# FPGA_DDR3_IO.net
KiCad netlist of a schematic drawn in Altium Designer
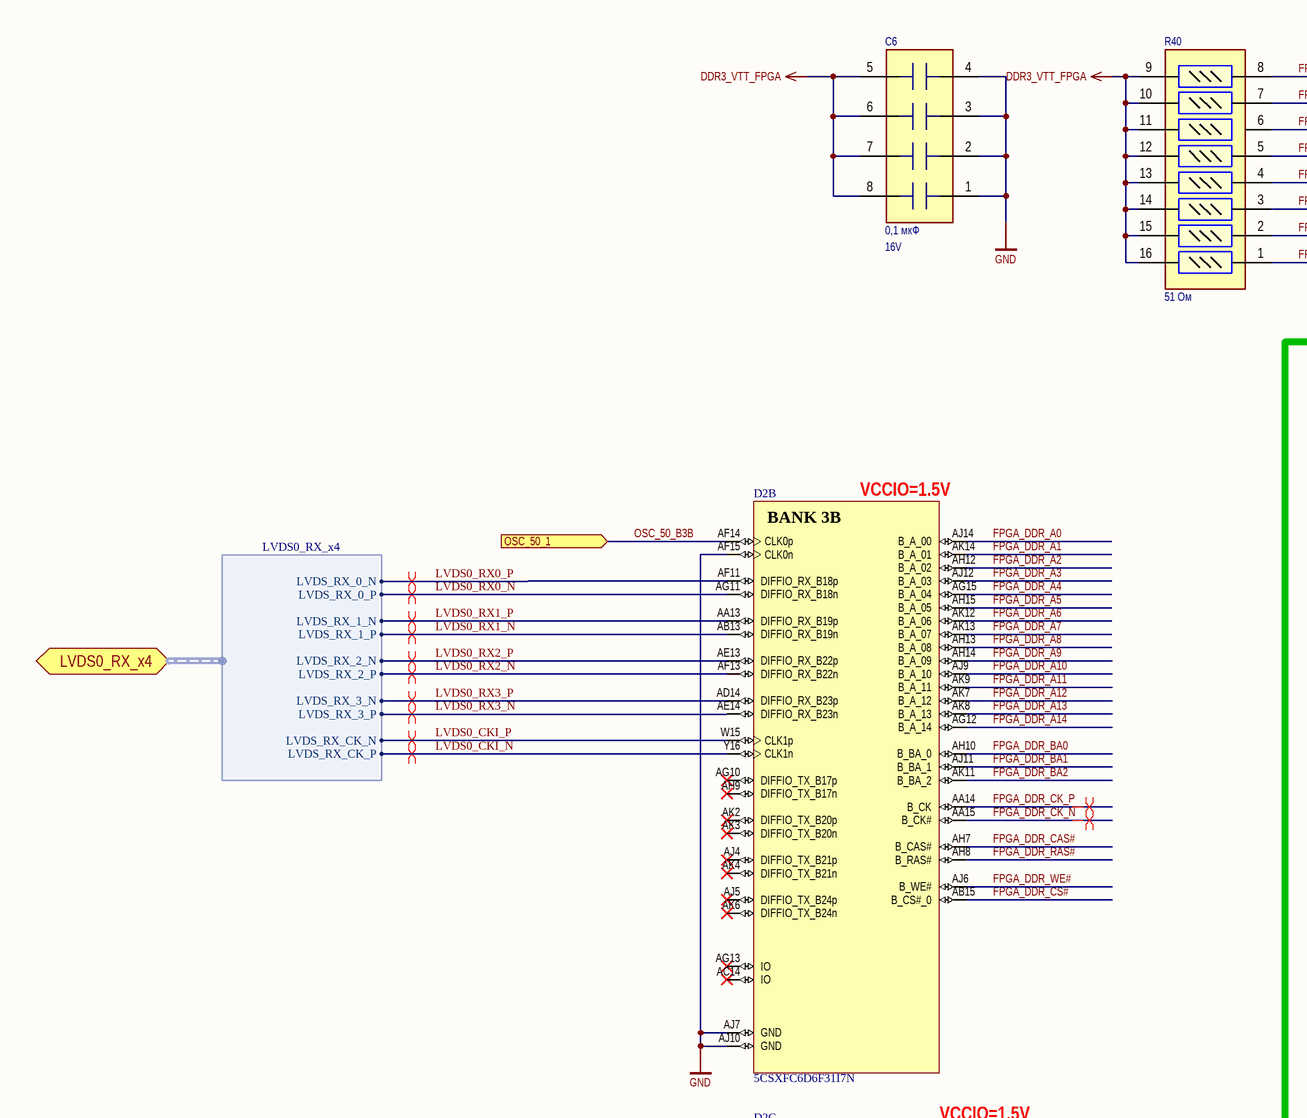
[diagram p0: FPGA_DDR3&IO.SchDoc, top left]
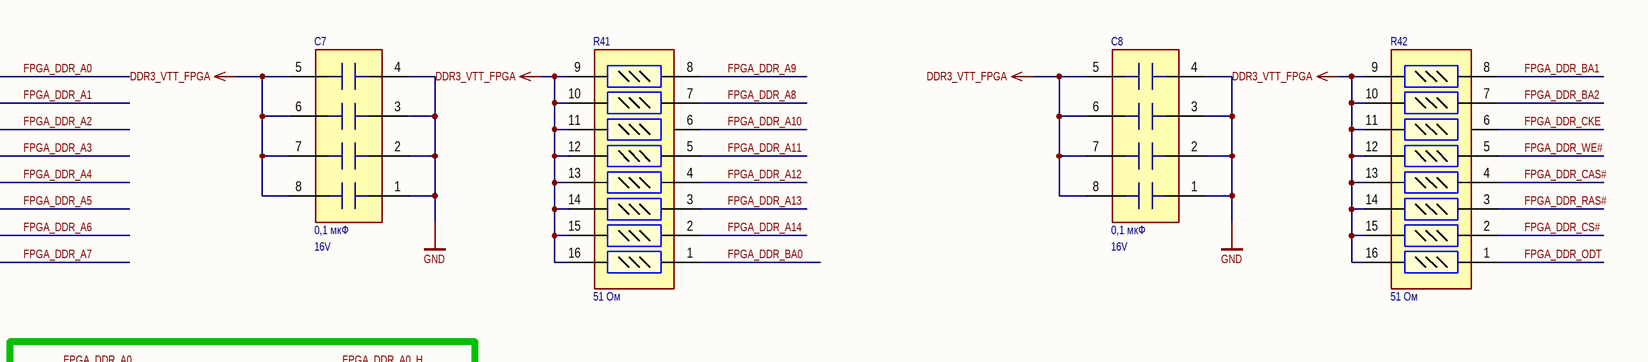
[diagram p1: FPGA_DDR3&IO.SchDoc, top right]
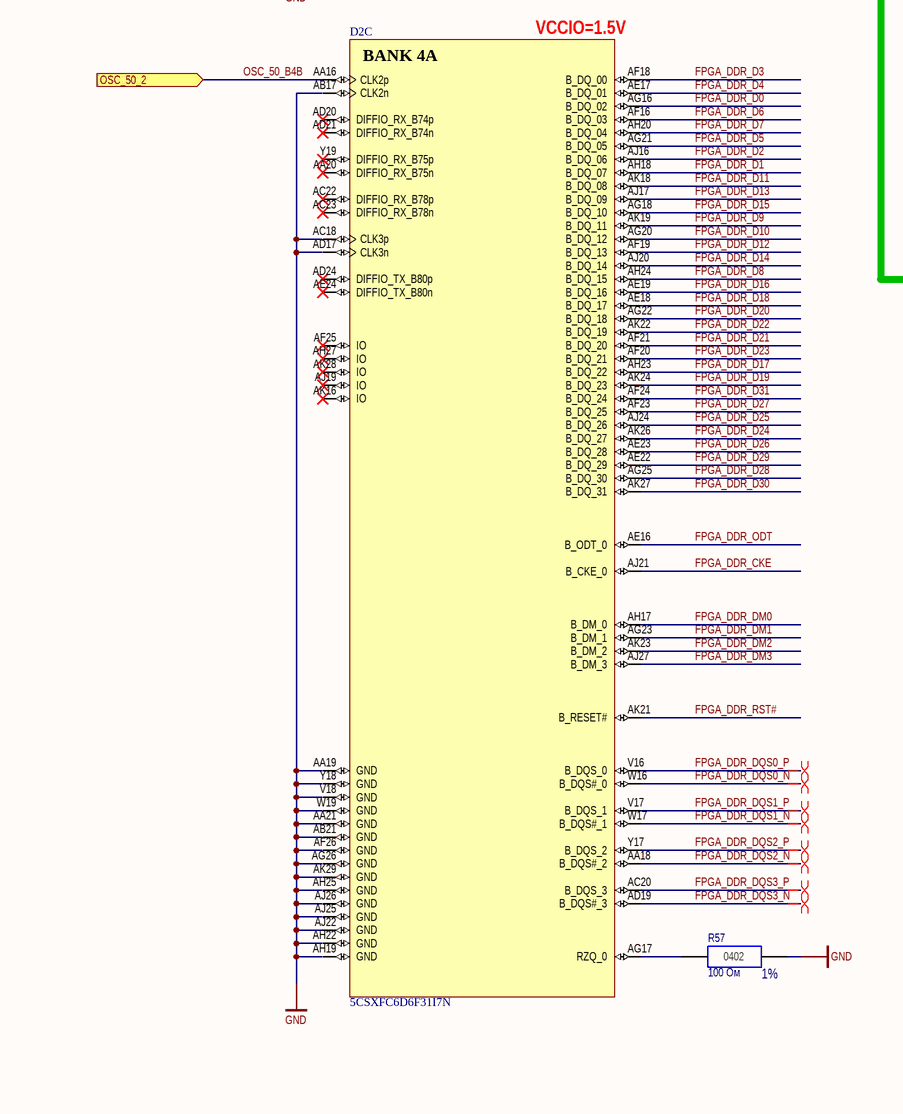
[diagram p2: FPGA_DDR3&IO.SchDoc, bottom left]
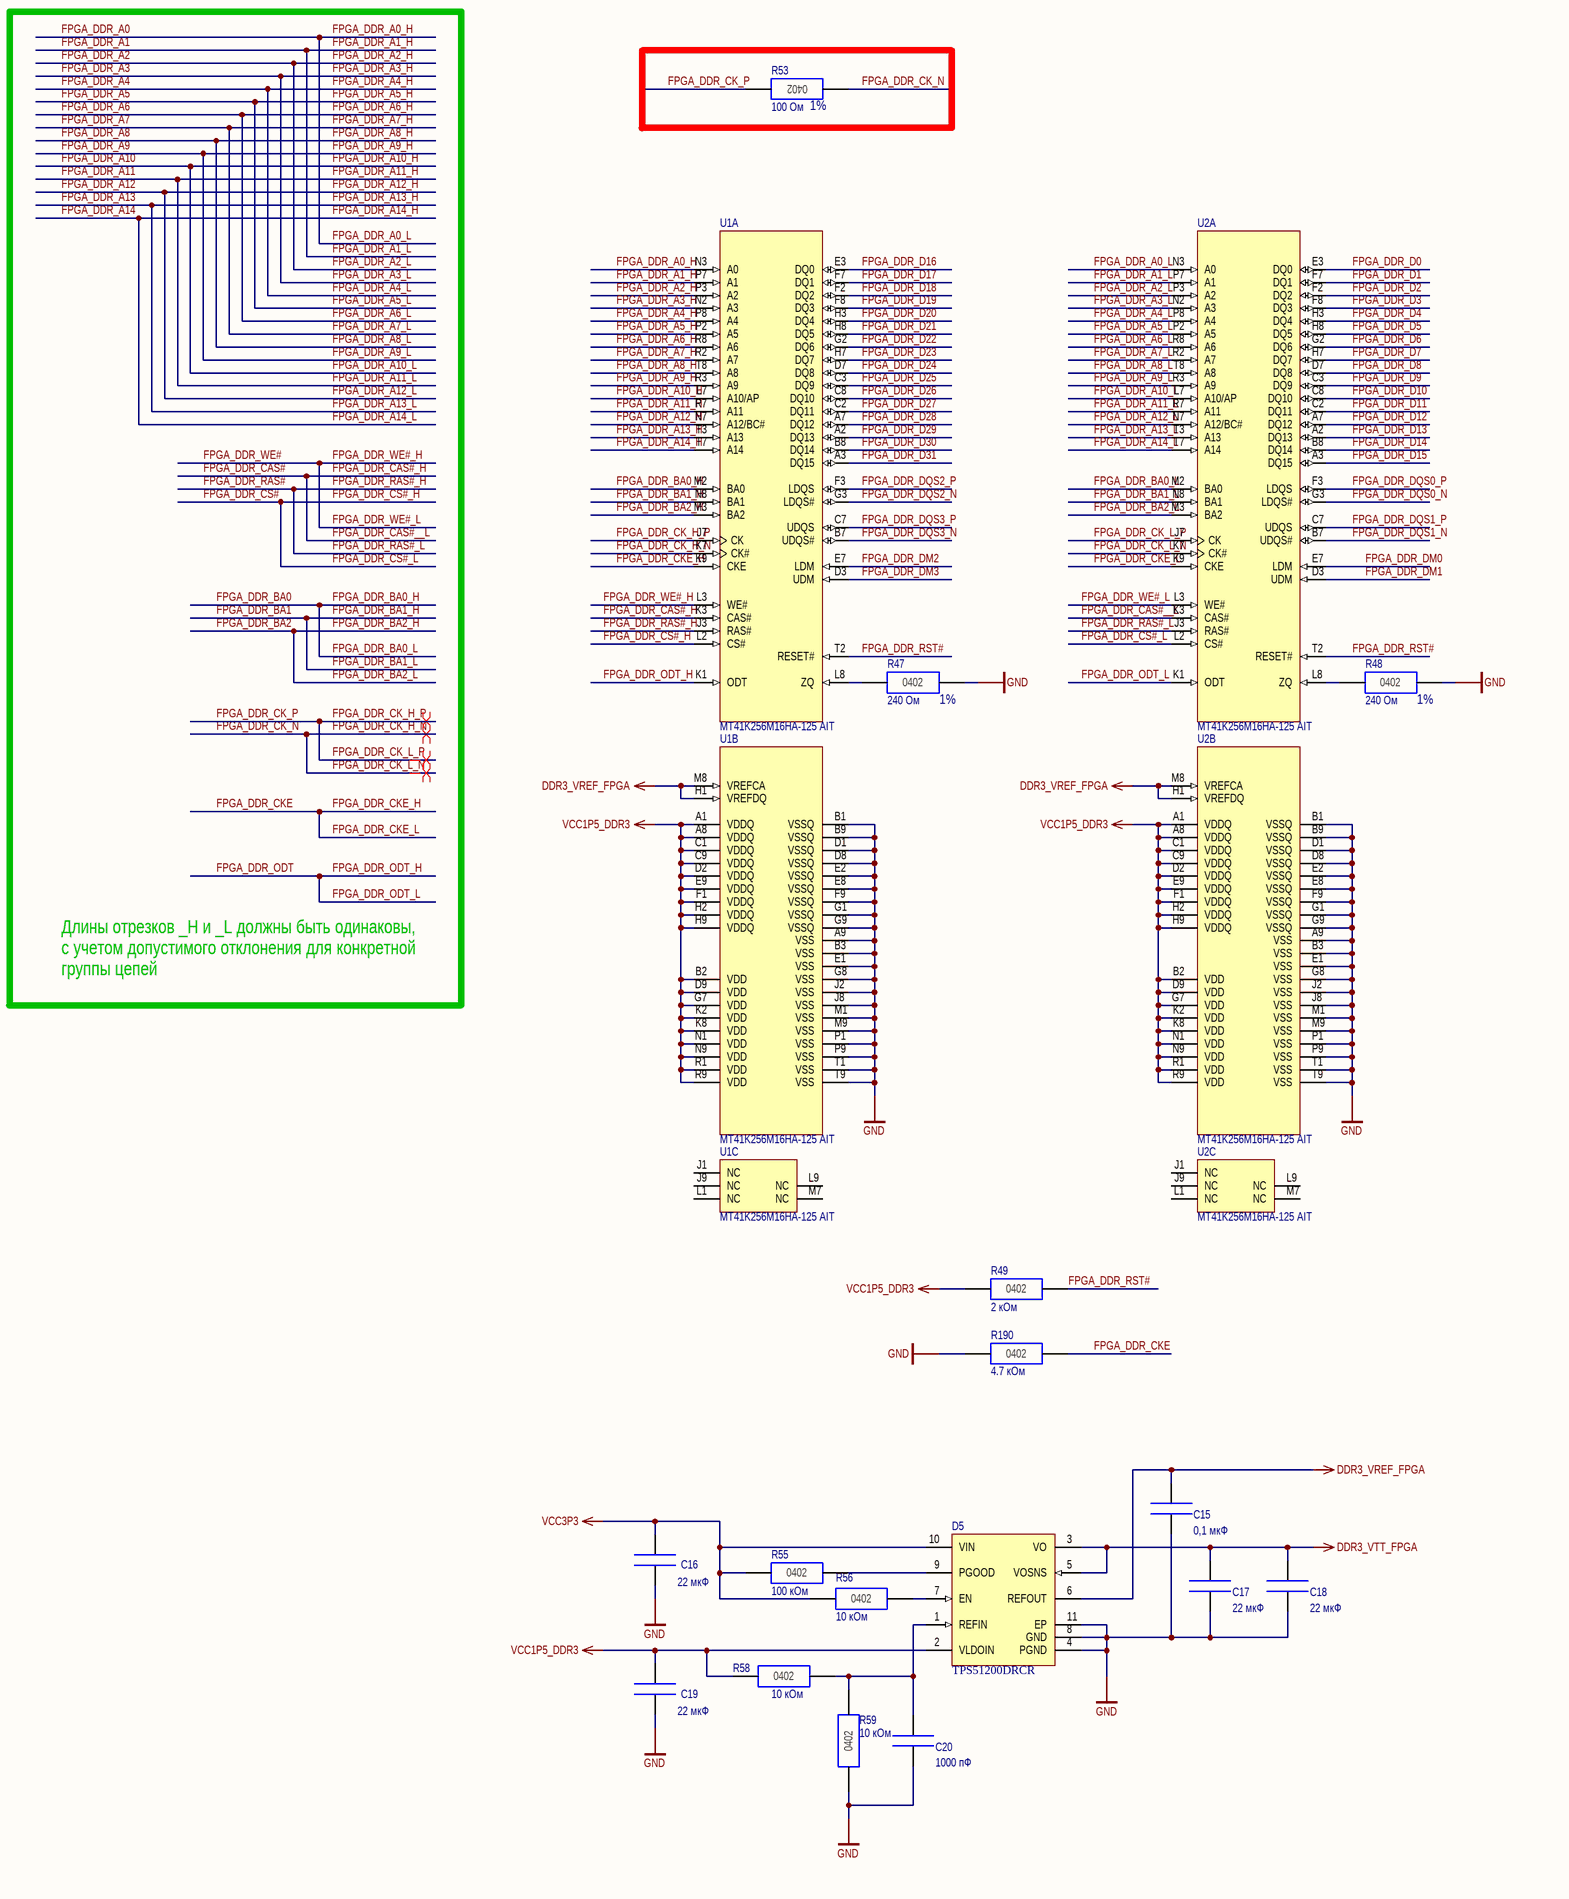
[diagram p3: FPGA_DDR3&IO.SchDoc, bottom right]

(export (version "E")
  (design (tool "Eeschema 10.0.6"))
  (components
    (comp (ref "C6")
      (value "0,1 мкФ")
      (footprint "CAF-80P319X159-8N")
      (description "Чип конденсатор керамический")
      (fields (field (name "V") "16V") (field (name "Comment") "W3A4YC104KAT2A"))
      (libsource (lib "SD_IC") (part "W3A4YC104KAT2A"))
    )
    (comp (ref "C7")
      (value "0,1 мкФ")
      (footprint "CAF-80P319X159-8N")
      (description "Чип конденсатор керамический")
      (fields (field (name "V") "16V") (field (name "Comment") "W3A4YC104KAT2A"))
      (libsource (lib "SD_IC") (part "W3A4YC104KAT2A"))
    )
    (comp (ref "C8")
      (value "0,1 мкФ")
      (footprint "CAF-80P319X159-8N")
      (description "Чип конденсатор керамический")
      (fields (field (name "V") "16V") (field (name "Comment") "W3A4YC104KAT2A"))
      (libsource (lib "SD_IC") (part "W3A4YC104KAT2A"))
    )
    (comp (ref "C15")
      (value "0,1 мкФ")
      (footprint "CC0402(1005)")
      (description "Чип конденсатор керамический")
      (fields (field (name "Comment") "CC0402-X7R-0,1 мкФ-20%-10В"))
      (libsource (lib "Чип конденсаторы") (part "CC0402-X7R-#-20%-10В"))
    )
    (comp (ref "C16")
      (value "22 мкФ")
      (footprint "CC0402(1005)")
      (description "Чип конденсатор керамический")
      (fields (field (name "Comment") "CC0402-X5R-22 мкФ-20%-6.3В"))
      (libsource (lib "Чип конденсаторы") (part "CC0402-X7R-#-20%-10В"))
    )
    (comp (ref "C17")
      (value "22 мкФ")
      (footprint "CC0402(1005)")
      (description "Чип конденсатор керамический")
      (fields (field (name "Comment") "CC0402-X5R-22 мкФ-20%-6.3В"))
      (libsource (lib "Чип конденсаторы") (part "CC0402-X7R-#-20%-10В"))
    )
    (comp (ref "C18")
      (value "22 мкФ")
      (footprint "CC0402(1005)")
      (description "Чип конденсатор керамический")
      (fields (field (name "Comment") "CC0402-X5R-22 мкФ-20%-6.3В"))
      (libsource (lib "Чип конденсаторы") (part "CC0402-X7R-#-20%-10В"))
    )
    (comp (ref "C19")
      (value "22 мкФ")
      (footprint "CC0402(1005)")
      (description "Чип конденсатор керамический")
      (fields (field (name "Comment") "CC0402-X5R-22 мкФ-20%-6.3В"))
      (libsource (lib "Чип конденсаторы") (part "CC0402-X7R-#-20%-10В"))
    )
    (comp (ref "C20")
      (value "1000 пФ")
      (footprint "CC0402(1005)")
      (description "Чип конденсатор керамический")
      (fields (field (name "Comment") "CC0402-NP01000 пФ-1%-50В"))
      (libsource (lib "Чип конденсаторы") (part "CC0402-X7R-#-20%-10В"))
    )
    (comp (ref "D2")
      (value "5CSXFC6D6F31I7N")
      (footprint "ALTR-FBGA896_A-200")
      (fields (field (name "MANUFACTURER") "Altera"))
      (libsource (lib "") (part "5CSXFC6D6F31I7N_1"))
    )
    (comp (ref "D5")
      (value "TPS51200DRCR")
      (footprint "TI-DRC10-2400X1650TP_V")
      (fields (field (name "MANUFACTURER") "Texas Instruments"))
      (libsource (lib "SD_IC") (part "TPS51200DRCR"))
    )
    (comp (ref "R40")
      (value "51 Ом")
      (footprint "YC248")
      (description "Набор чип резисторов")
      (fields (field (name "Comment") "YC248-JR-07-51 Ом"))
      (libsource (lib "SD_IC") (part "YC248-JR-07-#"))
    )
    (comp (ref "R41")
      (value "51 Ом")
      (footprint "VOU_SOM_Vlad:YC248")
      (description "Набор чип резисторов")
      (fields (field (name "Comment") "YC248-JR-07-51 Ом"))
      (libsource (lib "SD_IC") (part "YC248-JR-07-#"))
    )
    (comp (ref "R42")
      (value "51 Ом")
      (footprint "YC248")
      (description "Набор чип резисторов")
      (fields (field (name "Comment") "YC248-JR-07-51 Ом"))
      (libsource (lib "SD_IC") (part "YC248-JR-07-#"))
    )
    (comp (ref "R47")
      (value "240 Ом")
      (footprint "CR0402(1005)")
      (description "Чип резистор")
      (fields (field (name "TOLERANCE") "1%") (field (name "Comment") "CR0402-240 Ом-±TOLERANCE"))
      (libsource (lib "Резисторы") (part "CR0402-#-±5%"))
    )
    (comp (ref "R48")
      (value "240 Ом")
      (footprint "CR0402(1005)")
      (description "Чип резистор")
      (fields (field (name "TOLERANCE") "1%") (field (name "Comment") "CR0402-240 Ом-±TOLERANCE"))
      (libsource (lib "Резисторы") (part "CR0402-#-±5%"))
    )
    (comp (ref "R49")
      (value "2 кОм")
      (footprint "CR0402(1005)")
      (description "Чип резистор")
      (fields (field (name "TOLERANCE") "5%") (field (name "Comment") "CR0402-2 кОм-±5%"))
      (libsource (lib "Резисторы") (part "CR0402-#-±5%"))
    )
    (comp (ref "R53")
      (value "100 Ом")
      (footprint "CR0402(1005)")
      (description "Чип резистор")
      (fields (field (name "TOLERANCE") "1%") (field (name "Comment") "CR0402-100 Ом-±TOLERANCE"))
      (libsource (lib "") (part "CR0402-#-±5%_1"))
    )
    (comp (ref "R55")
      (value "100 кОм")
      (footprint "CR0402(1005)")
      (description "Чип резистор")
      (fields (field (name "TOLERANCE") "5%") (field (name "Comment") "CR0402-100 кОм-±5%"))
      (libsource (lib "Резисторы") (part "CR0402-#-±5%"))
    )
    (comp (ref "R56")
      (value "10 кОм")
      (footprint "CR0402(1005)")
      (description "Чип резистор")
      (fields (field (name "TOLERANCE") "5%") (field (name "Comment") "CR0402-10 кОм-±5%"))
      (libsource (lib "Резисторы") (part "CR0402-#-±5%"))
    )
    (comp (ref "R57")
      (value "100 Ом")
      (footprint "CC0402(1005)_OCT")
      (description "Чип резистор")
      (fields (field (name "TOLERANCE") "1%") (field (name "Comment") "CR0402-100 Ом-±TOLERANCE"))
      (libsource (lib "Резисторы") (part "CR0402-#-±5%"))
    )
    (comp (ref "R58")
      (value "10 кОм")
      (footprint "CR0402(1005)")
      (description "Чип резистор")
      (fields (field (name "TOLERANCE") "5%") (field (name "Comment") "CR0402-10 кОм-±5%"))
      (libsource (lib "Резисторы") (part "CR0402-#-±5%"))
    )
    (comp (ref "R59")
      (value "10 кОм")
      (footprint "CR0402(1005)")
      (description "Чип резистор")
      (fields (field (name "TOLERANCE") "5%") (field (name "Comment") "CR0402-10 кОм-±5%"))
      (libsource (lib "") (part "CR0402-#-±5%_2"))
    )
    (comp (ref "R190")
      (value "4.7 кОм")
      (footprint "CR0402(1005)")
      (description "Чип резистор")
      (fields (field (name "TOLERANCE") "5%") (field (name "Comment") "CR0402-4.7 кОм-±5%"))
      (libsource (lib "Резисторы") (part "CR0402-#-±5%"))
    )
    (comp (ref "U1")
      (value "MT41K256M16HA-125 AIT")
      (footprint "MICT-HA-96")
      (description "4Gb DDR3-1600 SDRAM, 256Mb x 16, 1.25ns, 1.35V, -40 to 95 degC, 96-Ball FBGA, Pb-Free")
      (fields (field (name "VOLTAGE") "1.35V ") (field (name "MANUFACTURER") "Micron"))
      (libsource (lib "SD_IC") (part "MT41K256M16HA-125 AIT"))
    )
    (comp (ref "U2")
      (value "MT41K256M16HA-125 AIT")
      (footprint "MICT-HA-96")
      (description "4Gb DDR3-1600 SDRAM, 256Mb x 16, 1.25ns, 1.35V, -40 to 95 degC, 96-Ball FBGA, Pb-Free")
      (fields (field (name "VOLTAGE") "1.35V ") (field (name "MANUFACTURER") "Micron"))
      (libsource (lib "SD_IC") (part "MT41K256M16HA-125 AIT"))
    )
  )
  (nets
    (net (code "2") (name "/FPGA_DDR_A0") (class "Default")
      (node (ref "D2") (pin "AJ14") (pinfunction "B_A_00_AJ14") (pintype "bidirectional"))
      (node (ref "R40") (pin "8") (pintype "passive"))
      (node (ref "U1") (pin "N3") (pinfunction "A0_N3") (pintype "input"))
      (node (ref "U2") (pin "N3") (pinfunction "A0_N3") (pintype "input"))
    )
    (net (code "3") (name "/FPGA_DDR_A1") (class "Default")
      (node (ref "D2") (pin "AK14") (pinfunction "B_A_01_AK14") (pintype "bidirectional"))
      (node (ref "R40") (pin "7") (pintype "passive"))
      (node (ref "U1") (pin "P7") (pinfunction "A1_P7") (pintype "input"))
      (node (ref "U2") (pin "P7") (pinfunction "A1_P7") (pintype "input"))
    )
    (net (code "4") (name "/FPGA_DDR_A2") (class "Default")
      (node (ref "D2") (pin "AH12") (pinfunction "B_A_02_AH12") (pintype "bidirectional"))
      (node (ref "R40") (pin "6") (pintype "passive"))
      (node (ref "U1") (pin "P3") (pinfunction "A2_P3") (pintype "input"))
      (node (ref "U2") (pin "P3") (pinfunction "A2_P3") (pintype "input"))
    )
    (net (code "5") (name "/FPGA_DDR_A3") (class "Default")
      (node (ref "D2") (pin "AJ12") (pinfunction "B_A_03_AJ12") (pintype "bidirectional"))
      (node (ref "R40") (pin "5") (pintype "passive"))
      (node (ref "U1") (pin "N2") (pinfunction "A3_N2") (pintype "input"))
      (node (ref "U2") (pin "N2") (pinfunction "A3_N2") (pintype "input"))
    )
    (net (code "6") (name "/FPGA_DDR_A4") (class "Default")
      (node (ref "D2") (pin "AG15") (pinfunction "B_A_04_AG15") (pintype "bidirectional"))
      (node (ref "R40") (pin "4") (pintype "passive"))
      (node (ref "U1") (pin "P8") (pinfunction "A4_P8") (pintype "input"))
      (node (ref "U2") (pin "P8") (pinfunction "A4_P8") (pintype "input"))
    )
    (net (code "7") (name "/FPGA_DDR_A5") (class "Default")
      (node (ref "D2") (pin "AH15") (pinfunction "B_A_05_AH15") (pintype "bidirectional"))
      (node (ref "R40") (pin "3") (pintype "passive"))
      (node (ref "U1") (pin "P2") (pinfunction "A5_P2") (pintype "input"))
      (node (ref "U2") (pin "P2") (pinfunction "A5_P2") (pintype "input"))
    )
    (net (code "8") (name "/FPGA_DDR_A6") (class "Default")
      (node (ref "D2") (pin "AK12") (pinfunction "B_A_06_AK12") (pintype "bidirectional"))
      (node (ref "R40") (pin "2") (pintype "passive"))
      (node (ref "U1") (pin "R8") (pinfunction "A6_R8") (pintype "input"))
      (node (ref "U2") (pin "R8") (pinfunction "A6_R8") (pintype "input"))
    )
    (net (code "9") (name "/FPGA_DDR_A7") (class "Default")
      (node (ref "D2") (pin "AK13") (pinfunction "B_A_07_AK13") (pintype "bidirectional"))
      (node (ref "R40") (pin "1") (pintype "passive"))
      (node (ref "U1") (pin "R2") (pinfunction "A7_R2") (pintype "input"))
      (node (ref "U2") (pin "R2") (pinfunction "A7_R2") (pintype "input"))
    )
    (net (code "10") (name "/FPGA_DDR_A8") (class "Default")
      (node (ref "D2") (pin "AH13") (pinfunction "B_A_08_AH13") (pintype "bidirectional"))
      (node (ref "R41") (pin "7") (pintype "passive"))
      (node (ref "U1") (pin "T8") (pinfunction "A8_T8") (pintype "input"))
      (node (ref "U2") (pin "T8") (pinfunction "A8_T8") (pintype "input"))
    )
    (net (code "11") (name "/FPGA_DDR_A9") (class "Default")
      (node (ref "D2") (pin "AH14") (pinfunction "B_A_09_AH14") (pintype "bidirectional"))
      (node (ref "R41") (pin "8") (pintype "passive"))
      (node (ref "U1") (pin "R3") (pinfunction "A9_R3") (pintype "input"))
      (node (ref "U2") (pin "R3") (pinfunction "A9_R3") (pintype "input"))
    )
    (net (code "12") (name "/FPGA_DDR_A10") (class "Default")
      (node (ref "D2") (pin "AJ9") (pinfunction "B_A_10_AJ9") (pintype "bidirectional"))
      (node (ref "R41") (pin "6") (pintype "passive"))
      (node (ref "U1") (pin "L7") (pinfunction "A10/AP_L7") (pintype "input"))
      (node (ref "U2") (pin "L7") (pinfunction "A10/AP_L7") (pintype "input"))
    )
    (net (code "13") (name "/FPGA_DDR_A11") (class "Default")
      (node (ref "D2") (pin "AK9") (pinfunction "B_A_11_AK9") (pintype "bidirectional"))
      (node (ref "R41") (pin "5") (pintype "passive"))
      (node (ref "U1") (pin "R7") (pinfunction "A11_R7") (pintype "input"))
      (node (ref "U2") (pin "R7") (pinfunction "A11_R7") (pintype "input"))
    )
    (net (code "14") (name "/FPGA_DDR_A12") (class "Default")
      (node (ref "D2") (pin "AK7") (pinfunction "B_A_12_AK7") (pintype "bidirectional"))
      (node (ref "R41") (pin "4") (pintype "passive"))
      (node (ref "U1") (pin "N7") (pinfunction "A12/BC#_N7") (pintype "input"))
      (node (ref "U2") (pin "N7") (pinfunction "A12/BC#_N7") (pintype "input"))
    )
    (net (code "15") (name "/FPGA_DDR_A13") (class "Default")
      (node (ref "D2") (pin "AK8") (pinfunction "B_A_13_AK8") (pintype "bidirectional"))
      (node (ref "R41") (pin "3") (pintype "passive"))
      (node (ref "U1") (pin "T3") (pinfunction "A13_T3") (pintype "input"))
      (node (ref "U2") (pin "T3") (pinfunction "A13_T3") (pintype "input"))
    )
    (net (code "16") (name "/FPGA_DDR_A14") (class "Default")
      (node (ref "D2") (pin "AG12") (pinfunction "B_A_14_AG12") (pintype "bidirectional"))
      (node (ref "R41") (pin "2") (pintype "passive"))
      (node (ref "U1") (pin "T7") (pinfunction "A14_T7") (pintype "input"))
      (node (ref "U2") (pin "T7") (pinfunction "A14_T7") (pintype "input"))
    )
    (net (code "17") (name "/FPGA_DDR_BA0") (class "Default")
      (node (ref "D2") (pin "AH10") (pinfunction "B_BA_0_AH10") (pintype "bidirectional"))
      (node (ref "R41") (pin "1") (pintype "passive"))
      (node (ref "U1") (pin "M2") (pinfunction "BA0_M2") (pintype "input"))
      (node (ref "U2") (pin "M2") (pinfunction "BA0_M2") (pintype "input"))
    )
    (net (code "18") (name "/FPGA_DDR_BA1") (class "Default")
      (node (ref "D2") (pin "AJ11") (pinfunction "B_BA_1_AJ11") (pintype "bidirectional"))
      (node (ref "R42") (pin "8") (pintype "passive"))
      (node (ref "U1") (pin "N8") (pinfunction "BA1_N8") (pintype "input"))
      (node (ref "U2") (pin "N8") (pinfunction "BA1_N8") (pintype "input"))
    )
    (net (code "19") (name "/FPGA_DDR_BA2") (class "Default")
      (node (ref "D2") (pin "AK11") (pinfunction "B_BA_2_AK11") (pintype "bidirectional"))
      (node (ref "R42") (pin "7") (pintype "passive"))
      (node (ref "U1") (pin "M3") (pinfunction "BA2_M3") (pintype "input"))
      (node (ref "U2") (pin "M3") (pinfunction "BA2_M3") (pintype "input"))
    )
    (net (code "20") (name "/FPGA_DDR_CAS#") (class "Default")
      (node (ref "D2") (pin "AH7") (pinfunction "B_CAS#_AH7") (pintype "bidirectional"))
      (node (ref "R42") (pin "4") (pintype "passive"))
      (node (ref "U1") (pin "K3") (pinfunction "CAS#_K3") (pintype "input"))
      (node (ref "U2") (pin "K3") (pinfunction "CAS#_K3") (pintype "input"))
    )
    (net (code "21") (name "/FPGA_DDR_CKE") (class "Default")
      (node (ref "D2") (pin "AJ21") (pinfunction "B_CKE_0_AJ21") (pintype "bidirectional"))
      (node (ref "R190") (pin "2") (pinfunction "-_2") (pintype "passive"))
      (node (ref "R42") (pin "6") (pintype "passive"))
      (node (ref "U1") (pin "K9") (pinfunction "CKE_K9") (pintype "input"))
      (node (ref "U2") (pin "K9") (pinfunction "CKE_K9") (pintype "input"))
    )
    (net (code "22") (name "/FPGA_DDR_CK_H_N") (class "Default")
      (node (ref "D2") (pin "AA15") (pinfunction "B_CK#_AA15") (pintype "bidirectional"))
      (node (ref "R53") (pin "1") (pinfunction "+_1") (pintype "passive"))
      (node (ref "U1") (pin "K7") (pinfunction "CK#_K7") (pintype "input"))
      (node (ref "U2") (pin "K7") (pinfunction "CK#_K7") (pintype "input"))
    )
    (net (code "23") (name "/FPGA_DDR_CK_H_P") (class "Default")
      (node (ref "D2") (pin "AA14") (pinfunction "B_CK_AA14") (pintype "bidirectional"))
      (node (ref "R53") (pin "2") (pinfunction "-_2") (pintype "passive"))
      (node (ref "U1") (pin "J7") (pinfunction "CK_J7") (pintype "input"))
      (node (ref "U2") (pin "J7") (pinfunction "CK_J7") (pintype "input"))
    )
    (net (code "24") (name "/FPGA_DDR_CS#") (class "Default")
      (node (ref "D2") (pin "AB15") (pinfunction "B_CS#_0_AB15") (pintype "bidirectional"))
      (node (ref "R42") (pin "2") (pintype "passive"))
      (node (ref "U1") (pin "L2") (pinfunction "CS#_L2") (pintype "input"))
      (node (ref "U2") (pin "L2") (pinfunction "CS#_L2") (pintype "input"))
    )
    (net (code "25") (name "/FPGA_DDR_D0") (class "Default")
      (node (ref "D2") (pin "AG16") (pinfunction "B_DQ_02_AG16") (pintype "bidirectional"))
      (node (ref "U2") (pin "E3") (pinfunction "DQ0_E3") (pintype "bidirectional"))
    )
    (net (code "26") (name "/FPGA_DDR_D1") (class "Default")
      (node (ref "D2") (pin "AH18") (pinfunction "B_DQ_07_AH18") (pintype "bidirectional"))
      (node (ref "U2") (pin "F7") (pinfunction "DQ1_F7") (pintype "bidirectional"))
    )
    (net (code "27") (name "/FPGA_DDR_D2") (class "Default")
      (node (ref "D2") (pin "AJ16") (pinfunction "B_DQ_06_AJ16") (pintype "bidirectional"))
      (node (ref "U2") (pin "F2") (pinfunction "DQ2_F2") (pintype "bidirectional"))
    )
    (net (code "28") (name "/FPGA_DDR_D3") (class "Default")
      (node (ref "D2") (pin "AF18") (pinfunction "B_DQ_00_AF18") (pintype "bidirectional"))
      (node (ref "U2") (pin "F8") (pinfunction "DQ3_F8") (pintype "bidirectional"))
    )
    (net (code "29") (name "/FPGA_DDR_D4") (class "Default")
      (node (ref "D2") (pin "AE17") (pinfunction "B_DQ_01_AE17") (pintype "bidirectional"))
      (node (ref "U2") (pin "H3") (pinfunction "DQ4_H3") (pintype "bidirectional"))
    )
    (net (code "30") (name "/FPGA_DDR_D5") (class "Default")
      (node (ref "D2") (pin "AG21") (pinfunction "B_DQ_05_AG21") (pintype "bidirectional"))
      (node (ref "U2") (pin "H8") (pinfunction "DQ5_H8") (pintype "bidirectional"))
    )
    (net (code "31") (name "/FPGA_DDR_D6") (class "Default")
      (node (ref "D2") (pin "AF16") (pinfunction "B_DQ_03_AF16") (pintype "bidirectional"))
      (node (ref "U2") (pin "G2") (pinfunction "DQ6_G2") (pintype "bidirectional"))
    )
    (net (code "32") (name "/FPGA_DDR_D7") (class "Default")
      (node (ref "D2") (pin "AH20") (pinfunction "B_DQ_04_AH20") (pintype "bidirectional"))
      (node (ref "U2") (pin "H7") (pinfunction "DQ7_H7") (pintype "bidirectional"))
    )
    (net (code "33") (name "/FPGA_DDR_D8") (class "Default")
      (node (ref "D2") (pin "AH24") (pinfunction "B_DQ_15_AH24") (pintype "bidirectional"))
      (node (ref "U2") (pin "D7") (pinfunction "DQ8_D7") (pintype "bidirectional"))
    )
    (net (code "34") (name "/FPGA_DDR_D9") (class "Default")
      (node (ref "D2") (pin "AK19") (pinfunction "B_DQ_11_AK19") (pintype "bidirectional"))
      (node (ref "U2") (pin "C3") (pinfunction "DQ9_C3") (pintype "bidirectional"))
    )
    (net (code "35") (name "/FPGA_DDR_D10") (class "Default")
      (node (ref "D2") (pin "AG20") (pinfunction "B_DQ_12_AG20") (pintype "bidirectional"))
      (node (ref "U2") (pin "C8") (pinfunction "DQ10_C8") (pintype "bidirectional"))
    )
    (net (code "36") (name "/FPGA_DDR_D11") (class "Default")
      (node (ref "D2") (pin "AK18") (pinfunction "B_DQ_08_AK18") (pintype "bidirectional"))
      (node (ref "U2") (pin "C2") (pinfunction "DQ11_C2") (pintype "bidirectional"))
    )
    (net (code "37") (name "/FPGA_DDR_D12") (class "Default")
      (node (ref "D2") (pin "AF19") (pinfunction "B_DQ_13_AF19") (pintype "bidirectional"))
      (node (ref "U2") (pin "A7") (pinfunction "DQ12_A7") (pintype "bidirectional"))
    )
    (net (code "38") (name "/FPGA_DDR_D13") (class "Default")
      (node (ref "D2") (pin "AJ17") (pinfunction "B_DQ_09_AJ17") (pintype "bidirectional"))
      (node (ref "U2") (pin "A2") (pinfunction "DQ13_A2") (pintype "bidirectional"))
    )
    (net (code "39") (name "/FPGA_DDR_D14") (class "Default")
      (node (ref "D2") (pin "AJ20") (pinfunction "B_DQ_14_AJ20") (pintype "bidirectional"))
      (node (ref "U2") (pin "B8") (pinfunction "DQ14_B8") (pintype "bidirectional"))
    )
    (net (code "40") (name "/FPGA_DDR_D15") (class "Default")
      (node (ref "D2") (pin "AG18") (pinfunction "B_DQ_10_AG18") (pintype "bidirectional"))
      (node (ref "U2") (pin "A3") (pinfunction "DQ15_A3") (pintype "bidirectional"))
    )
    (net (code "41") (name "/FPGA_DDR_D16") (class "Default")
      (node (ref "D2") (pin "AE19") (pinfunction "B_DQ_16_AE19") (pintype "bidirectional"))
      (node (ref "U1") (pin "E3") (pinfunction "DQ0_E3") (pintype "bidirectional"))
    )
    (net (code "42") (name "/FPGA_DDR_D17") (class "Default")
      (node (ref "D2") (pin "AH23") (pinfunction "B_DQ_22_AH23") (pintype "bidirectional"))
      (node (ref "U1") (pin "F7") (pinfunction "DQ1_F7") (pintype "bidirectional"))
    )
    (net (code "43") (name "/FPGA_DDR_D18") (class "Default")
      (node (ref "D2") (pin "AE18") (pinfunction "B_DQ_17_AE18") (pintype "bidirectional"))
      (node (ref "U1") (pin "F2") (pinfunction "DQ2_F2") (pintype "bidirectional"))
    )
    (net (code "44") (name "/FPGA_DDR_D19") (class "Default")
      (node (ref "D2") (pin "AK24") (pinfunction "B_DQ_23_AK24") (pintype "bidirectional"))
      (node (ref "U1") (pin "F8") (pinfunction "DQ3_F8") (pintype "bidirectional"))
    )
    (net (code "45") (name "/FPGA_DDR_D20") (class "Default")
      (node (ref "D2") (pin "AG22") (pinfunction "B_DQ_18_AG22") (pintype "bidirectional"))
      (node (ref "U1") (pin "H3") (pinfunction "DQ4_H3") (pintype "bidirectional"))
    )
    (net (code "46") (name "/FPGA_DDR_D21") (class "Default")
      (node (ref "D2") (pin "AF21") (pinfunction "B_DQ_20_AF21") (pintype "bidirectional"))
      (node (ref "U1") (pin "H8") (pinfunction "DQ5_H8") (pintype "bidirectional"))
    )
    (net (code "47") (name "/FPGA_DDR_D22") (class "Default")
      (node (ref "D2") (pin "AK22") (pinfunction "B_DQ_19_AK22") (pintype "bidirectional"))
      (node (ref "U1") (pin "G2") (pinfunction "DQ6_G2") (pintype "bidirectional"))
    )
    (net (code "48") (name "/FPGA_DDR_D23") (class "Default")
      (node (ref "D2") (pin "AF20") (pinfunction "B_DQ_21_AF20") (pintype "bidirectional"))
      (node (ref "U1") (pin "H7") (pinfunction "DQ7_H7") (pintype "bidirectional"))
    )
    (net (code "49") (name "/FPGA_DDR_D24") (class "Default")
      (node (ref "D2") (pin "AK26") (pinfunction "B_DQ_27_AK26") (pintype "bidirectional"))
      (node (ref "U1") (pin "D7") (pinfunction "DQ8_D7") (pintype "bidirectional"))
    )
    (net (code "50") (name "/FPGA_DDR_D25") (class "Default")
      (node (ref "D2") (pin "AJ24") (pinfunction "B_DQ_26_AJ24") (pintype "bidirectional"))
      (node (ref "U1") (pin "C3") (pinfunction "DQ9_C3") (pintype "bidirectional"))
    )
    (net (code "51") (name "/FPGA_DDR_D26") (class "Default")
      (node (ref "D2") (pin "AE23") (pinfunction "B_DQ_28_AE23") (pintype "bidirectional"))
      (node (ref "U1") (pin "C8") (pinfunction "DQ10_C8") (pintype "bidirectional"))
    )
    (net (code "52") (name "/FPGA_DDR_D27") (class "Default")
      (node (ref "D2") (pin "AF23") (pinfunction "B_DQ_25_AF23") (pintype "bidirectional"))
      (node (ref "U1") (pin "C2") (pinfunction "DQ11_C2") (pintype "bidirectional"))
    )
    (net (code "53") (name "/FPGA_DDR_D28") (class "Default")
      (node (ref "D2") (pin "AG25") (pinfunction "B_DQ_30_AG25") (pintype "bidirectional"))
      (node (ref "U1") (pin "A7") (pinfunction "DQ12_A7") (pintype "bidirectional"))
    )
    (net (code "54") (name "/FPGA_DDR_D29") (class "Default")
      (node (ref "D2") (pin "AE22") (pinfunction "B_DQ_29_AE22") (pintype "bidirectional"))
      (node (ref "U1") (pin "A2") (pinfunction "DQ13_A2") (pintype "bidirectional"))
    )
    (net (code "55") (name "/FPGA_DDR_D30") (class "Default")
      (node (ref "D2") (pin "AK27") (pinfunction "B_DQ_31_AK27") (pintype "bidirectional"))
      (node (ref "U1") (pin "B8") (pinfunction "DQ14_B8") (pintype "bidirectional"))
    )
    (net (code "56") (name "/FPGA_DDR_D31") (class "Default")
      (node (ref "D2") (pin "AF24") (pinfunction "B_DQ_24_AF24") (pintype "bidirectional"))
      (node (ref "U1") (pin "A3") (pinfunction "DQ15_A3") (pintype "bidirectional"))
    )
    (net (code "57") (name "/FPGA_DDR_DM0") (class "Default")
      (node (ref "D2") (pin "AH17") (pinfunction "B_DM_0_AH17") (pintype "bidirectional"))
      (node (ref "U2") (pin "E7") (pinfunction "LDM_E7") (pintype "input"))
    )
    (net (code "58") (name "/FPGA_DDR_DM1") (class "Default")
      (node (ref "D2") (pin "AG23") (pinfunction "B_DM_1_AG23") (pintype "bidirectional"))
      (node (ref "U2") (pin "D3") (pinfunction "UDM_D3") (pintype "input"))
    )
    (net (code "59") (name "/FPGA_DDR_DM2") (class "Default")
      (node (ref "D2") (pin "AK23") (pinfunction "B_DM_2_AK23") (pintype "bidirectional"))
      (node (ref "U1") (pin "E7") (pinfunction "LDM_E7") (pintype "input"))
    )
    (net (code "60") (name "/FPGA_DDR_DM3") (class "Default")
      (node (ref "D2") (pin "AJ27") (pinfunction "B_DM_3_AJ27") (pintype "bidirectional"))
      (node (ref "U1") (pin "D3") (pinfunction "UDM_D3") (pintype "input"))
    )
    (net (code "61") (name "/FPGA_DDR_DQS0_N") (class "Default")
      (node (ref "D2") (pin "W16") (pinfunction "B_DQS#_0_W16") (pintype "bidirectional"))
      (node (ref "U2") (pin "G3") (pinfunction "LDQS#_G3") (pintype "bidirectional"))
    )
    (net (code "62") (name "/FPGA_DDR_DQS0_P") (class "Default")
      (node (ref "D2") (pin "V16") (pinfunction "B_DQS_0_V16") (pintype "bidirectional"))
      (node (ref "U2") (pin "F3") (pinfunction "LDQS_F3") (pintype "bidirectional"))
    )
    (net (code "63") (name "/FPGA_DDR_DQS1_N") (class "Default")
      (node (ref "D2") (pin "W17") (pinfunction "B_DQS#_1_W17") (pintype "bidirectional"))
      (node (ref "U2") (pin "B7") (pinfunction "UDQS#_B7") (pintype "bidirectional"))
    )
    (net (code "64") (name "/FPGA_DDR_DQS1_P") (class "Default")
      (node (ref "D2") (pin "V17") (pinfunction "B_DQS_1_V17") (pintype "bidirectional"))
      (node (ref "U2") (pin "C7") (pinfunction "UDQS_C7") (pintype "bidirectional"))
    )
    (net (code "65") (name "/FPGA_DDR_DQS2_N") (class "Default")
      (node (ref "D2") (pin "AA18") (pinfunction "B_DQS#_2_AA18") (pintype "bidirectional"))
      (node (ref "U1") (pin "G3") (pinfunction "LDQS#_G3") (pintype "bidirectional"))
    )
    (net (code "66") (name "/FPGA_DDR_DQS2_P") (class "Default")
      (node (ref "D2") (pin "Y17") (pinfunction "B_DQS_2_Y17") (pintype "bidirectional"))
      (node (ref "U1") (pin "F3") (pinfunction "LDQS_F3") (pintype "bidirectional"))
    )
    (net (code "67") (name "/FPGA_DDR_DQS3_N") (class "Default")
      (node (ref "D2") (pin "AD19") (pinfunction "B_DQS#_3_AD19") (pintype "bidirectional"))
      (node (ref "U1") (pin "B7") (pinfunction "UDQS#_B7") (pintype "bidirectional"))
    )
    (net (code "68") (name "/FPGA_DDR_DQS3_P") (class "Default")
      (node (ref "D2") (pin "AC20") (pinfunction "B_DQS_3_AC20") (pintype "bidirectional"))
      (node (ref "U1") (pin "C7") (pinfunction "UDQS_C7") (pintype "bidirectional"))
    )
    (net (code "69") (name "/FPGA_DDR_ODT") (class "Default")
      (node (ref "D2") (pin "AE16") (pinfunction "B_ODT_0_AE16") (pintype "bidirectional"))
      (node (ref "R42") (pin "1") (pintype "passive"))
      (node (ref "U1") (pin "K1") (pinfunction "ODT_K1") (pintype "input"))
      (node (ref "U2") (pin "K1") (pinfunction "ODT_K1") (pintype "input"))
    )
    (net (code "70") (name "/FPGA_DDR_RAS#") (class "Default")
      (node (ref "D2") (pin "AH8") (pinfunction "B_RAS#_AH8") (pintype "bidirectional"))
      (node (ref "R42") (pin "3") (pintype "passive"))
      (node (ref "U1") (pin "J3") (pinfunction "RAS#_J3") (pintype "input"))
      (node (ref "U2") (pin "J3") (pinfunction "RAS#_J3") (pintype "input"))
    )
    (net (code "71") (name "/FPGA_DDR_RST#") (class "Default")
      (node (ref "D2") (pin "AK21") (pinfunction "B_RESET#_AK21") (pintype "bidirectional"))
      (node (ref "R49") (pin "2") (pinfunction "-_2") (pintype "passive"))
      (node (ref "U1") (pin "T2") (pinfunction "RESET#_T2") (pintype "input"))
      (node (ref "U2") (pin "T2") (pinfunction "RESET#_T2") (pintype "input"))
    )
    (net (code "72") (name "/FPGA_DDR_WE#") (class "Default")
      (node (ref "D2") (pin "AJ6") (pinfunction "B_WE#_AJ6") (pintype "bidirectional"))
      (node (ref "R42") (pin "5") (pintype "passive"))
      (node (ref "U1") (pin "L3") (pinfunction "WE#_L3") (pintype "input"))
      (node (ref "U2") (pin "L3") (pinfunction "WE#_L3") (pintype "input"))
    )
    (net (code "74") (name "/LVDS0_CKI_P") (class "Default")
      (node (ref "D2") (pin "W15") (pinfunction "CLK1p_W15") (pintype "bidirectional"))
    )
    (net (code "76") (name "/LVDS0_RX0_P") (class "Default")
      (node (ref "D2") (pin "AF11") (pinfunction "DIFFIO_RX_B18p_AF11") (pintype "bidirectional"))
    )
    (net (code "77") (name "/LVDS0_RX1_N") (class "Default")
      (node (ref "D2") (pin "AB13") (pinfunction "DIFFIO_RX_B19n_AB13") (pintype "bidirectional"))
    )
    (net (code "78") (name "/LVDS0_RX1_P") (class "Default")
      (node (ref "D2") (pin "AA13") (pinfunction "DIFFIO_RX_B19p_AA13") (pintype "bidirectional"))
    )
    (net (code "79") (name "/LVDS0_RX2_N") (class "Default")
      (node (ref "D2") (pin "AF13") (pinfunction "DIFFIO_RX_B22n_AF13") (pintype "bidirectional"))
    )
    (net (code "80") (name "/LVDS0_RX2_P") (class "Default")
      (node (ref "D2") (pin "AE13") (pinfunction "DIFFIO_RX_B22p_AE13") (pintype "bidirectional"))
    )
    (net (code "82") (name "/LVDS0_RX3_N") (class "Default")
      (node (ref "D2") (pin "AE14") (pinfunction "DIFFIO_RX_B23n_AE14") (pintype "bidirectional"))
    )
    (net (code "83") (name "/LVDS0_RX3_P") (class "Default")
      (node (ref "D2") (pin "AD14") (pinfunction "DIFFIO_RX_B23p_AD14") (pintype "bidirectional"))
    )
    (net (code "84") (name "/OSC_50_B3B") (class "Default")
      (node (ref "D2") (pin "AF14") (pinfunction "CLK0p_AF14") (pintype "bidirectional"))
    )
    (net (code "86") (name "/OSC_50_B4B") (class "Default")
      (node (ref "D2") (pin "AA16") (pinfunction "CLK2p_AA16") (pintype "bidirectional"))
    )
    (net (code "87") (name "DDR3_VREF_FPGA") (class "Default")
      (node (ref "C15") (pin "1") (pinfunction "+_1") (pintype "passive"))
      (node (ref "D5") (pin "6") (pinfunction "REFOUT_6") (pintype "power_in"))
      (node (ref "U1") (pin "H1") (pinfunction "VREFDQ_H1") (pintype "input"))
      (node (ref "U1") (pin "M8") (pinfunction "VREFCA_M8") (pintype "input"))
      (node (ref "U2") (pin "H1") (pinfunction "VREFDQ_H1") (pintype "input"))
      (node (ref "U2") (pin "M8") (pinfunction "VREFCA_M8") (pintype "input"))
    )
    (net (code "88") (name "DDR3_VTT_FPGA") (class "Default")
      (node (ref "C17") (pin "1") (pinfunction "+_1") (pintype "passive"))
      (node (ref "C18") (pin "1") (pinfunction "+_1") (pintype "passive"))
      (node (ref "C6") (pin "5") (pintype "passive"))
      (node (ref "C6") (pin "6") (pintype "passive"))
      (node (ref "C6") (pin "7") (pintype "passive"))
      (node (ref "C6") (pin "8") (pintype "passive"))
      (node (ref "C7") (pin "5") (pintype "passive"))
      (node (ref "C7") (pin "6") (pintype "passive"))
      (node (ref "C7") (pin "7") (pintype "passive"))
      (node (ref "C7") (pin "8") (pintype "passive"))
      (node (ref "C8") (pin "5") (pintype "passive"))
      (node (ref "C8") (pin "6") (pintype "passive"))
      (node (ref "C8") (pin "7") (pintype "passive"))
      (node (ref "C8") (pin "8") (pintype "passive"))
      (node (ref "D5") (pin "3") (pinfunction "VO_3") (pintype "power_in"))
      (node (ref "D5") (pin "5") (pinfunction "VOSNS_5") (pintype "input"))
      (node (ref "R40") (pin "10") (pintype "passive"))
      (node (ref "R40") (pin "11") (pintype "passive"))
      (node (ref "R40") (pin "12") (pintype "passive"))
      (node (ref "R40") (pin "13") (pintype "passive"))
      (node (ref "R40") (pin "14") (pintype "passive"))
      (node (ref "R40") (pin "15") (pintype "passive"))
      (node (ref "R40") (pin "16") (pintype "passive"))
      (node (ref "R40") (pin "9") (pintype "passive"))
      (node (ref "R41") (pin "10") (pintype "passive"))
      (node (ref "R41") (pin "11") (pintype "passive"))
      (node (ref "R41") (pin "12") (pintype "passive"))
      (node (ref "R41") (pin "13") (pintype "passive"))
      (node (ref "R41") (pin "14") (pintype "passive"))
      (node (ref "R41") (pin "15") (pintype "passive"))
      (node (ref "R41") (pin "16") (pintype "passive"))
      (node (ref "R41") (pin "9") (pintype "passive"))
      (node (ref "R42") (pin "10") (pintype "passive"))
      (node (ref "R42") (pin "11") (pintype "passive"))
      (node (ref "R42") (pin "12") (pintype "passive"))
      (node (ref "R42") (pin "13") (pintype "passive"))
      (node (ref "R42") (pin "14") (pintype "passive"))
      (node (ref "R42") (pin "15") (pintype "passive"))
      (node (ref "R42") (pin "16") (pintype "passive"))
      (node (ref "R42") (pin "9") (pintype "passive"))
    )
    (net (code "89") (name "GND") (class "Default")
      (node (ref "C15") (pin "2") (pinfunction "-_2") (pintype "passive"))
      (node (ref "C16") (pin "2") (pinfunction "-_2") (pintype "passive"))
      (node (ref "C17") (pin "2") (pinfunction "-_2") (pintype "passive"))
      (node (ref "C18") (pin "2") (pinfunction "-_2") (pintype "passive"))
      (node (ref "C19") (pin "2") (pinfunction "-_2") (pintype "passive"))
      (node (ref "C20") (pin "2") (pinfunction "-_2") (pintype "passive"))
      (node (ref "C6") (pin "1") (pintype "passive"))
      (node (ref "C6") (pin "2") (pintype "passive"))
      (node (ref "C6") (pin "3") (pintype "passive"))
      (node (ref "C6") (pin "4") (pintype "passive"))
      (node (ref "C7") (pin "1") (pintype "passive"))
      (node (ref "C7") (pin "2") (pintype "passive"))
      (node (ref "C7") (pin "3") (pintype "passive"))
      (node (ref "C7") (pin "4") (pintype "passive"))
      (node (ref "C8") (pin "1") (pintype "passive"))
      (node (ref "C8") (pin "2") (pintype "passive"))
      (node (ref "C8") (pin "3") (pintype "passive"))
      (node (ref "C8") (pin "4") (pintype "passive"))
      (node (ref "D2") (pin "AF15") (pinfunction "CLK0n_AF15") (pintype "bidirectional"))
      (node (ref "D2") (pin "AJ10") (pinfunction "GND_AJ10") (pintype "bidirectional"))
      (node (ref "D2") (pin "AJ22") (pinfunction "GND_AJ22") (pintype "bidirectional"))
      (node (ref "D2") (pin "AJ7") (pinfunction "GND_AJ7") (pintype "bidirectional"))
      (node (ref "D5") (pin "11") (pinfunction "EP_11") (pintype "power_in"))
      (node (ref "D5") (pin "4") (pinfunction "PGND_4") (pintype "power_in"))
      (node (ref "D5") (pin "8") (pinfunction "GND_8") (pintype "power_in"))
      (node (ref "R190") (pin "1") (pinfunction "+_1") (pintype "passive"))
      (node (ref "R47") (pin "2") (pinfunction "-_2") (pintype "passive"))
      (node (ref "R48") (pin "2") (pinfunction "-_2") (pintype "passive"))
      (node (ref "R57") (pin "2") (pinfunction "-_2") (pintype "passive"))
      (node (ref "R59") (pin "1") (pinfunction "+_1") (pintype "passive"))
      (node (ref "U1") (pin "A9") (pinfunction "VSS_A9") (pintype "power_in"))
      (node (ref "U1") (pin "B1") (pinfunction "VSSQ_B1") (pintype "power_in"))
      (node (ref "U1") (pin "B3") (pinfunction "VSS_B3") (pintype "power_in"))
      (node (ref "U1") (pin "B9") (pinfunction "VSSQ_B9") (pintype "power_in"))
      (node (ref "U1") (pin "D1") (pinfunction "VSSQ_D1") (pintype "power_in"))
      (node (ref "U1") (pin "D8") (pinfunction "VSSQ_D8") (pintype "power_in"))
      (node (ref "U1") (pin "E1") (pinfunction "VSS_E1") (pintype "power_in"))
      (node (ref "U1") (pin "E2") (pinfunction "VSSQ_E2") (pintype "power_in"))
      (node (ref "U1") (pin "E8") (pinfunction "VSSQ_E8") (pintype "power_in"))
      (node (ref "U1") (pin "F9") (pinfunction "VSSQ_F9") (pintype "power_in"))
      (node (ref "U1") (pin "G1") (pinfunction "VSSQ_G1") (pintype "power_in"))
      (node (ref "U1") (pin "G8") (pinfunction "VSS_G8") (pintype "power_in"))
      (node (ref "U1") (pin "G9") (pinfunction "VSSQ_G9") (pintype "power_in"))
      (node (ref "U1") (pin "J2") (pinfunction "VSS_J2") (pintype "power_in"))
      (node (ref "U1") (pin "J8") (pinfunction "VSS_J8") (pintype "power_in"))
      (node (ref "U1") (pin "M1") (pinfunction "VSS_M1") (pintype "power_in"))
      (node (ref "U1") (pin "M9") (pinfunction "VSS_M9") (pintype "power_in"))
      (node (ref "U1") (pin "P1") (pinfunction "VSS_P1") (pintype "power_in"))
      (node (ref "U1") (pin "P9") (pinfunction "VSS_P9") (pintype "power_in"))
      (node (ref "U1") (pin "T1") (pinfunction "VSS_T1") (pintype "power_in"))
      (node (ref "U1") (pin "T9") (pinfunction "VSS_T9") (pintype "power_in"))
      (node (ref "U2") (pin "A9") (pinfunction "VSS_A9") (pintype "power_in"))
      (node (ref "U2") (pin "B1") (pinfunction "VSSQ_B1") (pintype "power_in"))
      (node (ref "U2") (pin "B3") (pinfunction "VSS_B3") (pintype "power_in"))
      (node (ref "U2") (pin "B9") (pinfunction "VSSQ_B9") (pintype "power_in"))
      (node (ref "U2") (pin "D1") (pinfunction "VSSQ_D1") (pintype "power_in"))
      (node (ref "U2") (pin "D8") (pinfunction "VSSQ_D8") (pintype "power_in"))
      (node (ref "U2") (pin "E1") (pinfunction "VSS_E1") (pintype "power_in"))
      (node (ref "U2") (pin "E2") (pinfunction "VSSQ_E2") (pintype "power_in"))
      (node (ref "U2") (pin "E8") (pinfunction "VSSQ_E8") (pintype "power_in"))
      (node (ref "U2") (pin "F9") (pinfunction "VSSQ_F9") (pintype "power_in"))
      (node (ref "U2") (pin "G1") (pinfunction "VSSQ_G1") (pintype "power_in"))
      (node (ref "U2") (pin "G8") (pinfunction "VSS_G8") (pintype "power_in"))
      (node (ref "U2") (pin "G9") (pinfunction "VSSQ_G9") (pintype "power_in"))
      (node (ref "U2") (pin "J2") (pinfunction "VSS_J2") (pintype "power_in"))
      (node (ref "U2") (pin "J8") (pinfunction "VSS_J8") (pintype "power_in"))
      (node (ref "U2") (pin "M1") (pinfunction "VSS_M1") (pintype "power_in"))
      (node (ref "U2") (pin "M9") (pinfunction "VSS_M9") (pintype "power_in"))
      (node (ref "U2") (pin "P1") (pinfunction "VSS_P1") (pintype "power_in"))
      (node (ref "U2") (pin "P9") (pinfunction "VSS_P9") (pintype "power_in"))
      (node (ref "U2") (pin "T1") (pinfunction "VSS_T1") (pintype "power_in"))
      (node (ref "U2") (pin "T9") (pinfunction "VSS_T9") (pintype "power_in"))
    )
    (net (code "90") (name "Net-(C20-+)") (class "Default")
      (node (ref "C20") (pin "1") (pinfunction "+_1") (pintype "passive"))
      (node (ref "D5") (pin "1") (pinfunction "REFIN_1") (pintype "input"))
      (node (ref "R58") (pin "2") (pinfunction "-_2") (pintype "passive"))
      (node (ref "R59") (pin "2") (pinfunction "-_2") (pintype "passive"))
    )
    (net (code "91") (name "Net-(D2C-RZQ_0)") (class "Default")
      (node (ref "D2") (pin "AG17") (pinfunction "RZQ_0_AG17") (pintype "bidirectional"))
      (node (ref "R57") (pin "1") (pinfunction "+_1") (pintype "passive"))
    )
    (net (code "92") (name "Net-(D5-EN)") (class "Default")
      (node (ref "D5") (pin "7") (pinfunction "EN_7") (pintype "input"))
      (node (ref "R56") (pin "2") (pinfunction "-_2") (pintype "passive"))
    )
    (net (code "93") (name "Net-(D5-PGOOD)") (class "Default")
      (node (ref "D5") (pin "9") (pinfunction "PGOOD_9") (pintype "open_collector"))
      (node (ref "R55") (pin "2") (pinfunction "-_2") (pintype "passive"))
    )
    (net (code "94") (name "Net-(R47-+)") (class "Default")
      (node (ref "R47") (pin "1") (pinfunction "+_1") (pintype "passive"))
      (node (ref "U1") (pin "L8") (pinfunction "ZQ_L8") (pintype "input"))
    )
    (net (code "95") (name "Net-(R48-+)") (class "Default")
      (node (ref "R48") (pin "1") (pinfunction "+_1") (pintype "passive"))
      (node (ref "U2") (pin "L8") (pinfunction "ZQ_L8") (pintype "input"))
    )
    (net (code "96") (name "VCC1P5_DDR3") (class "Default")
      (node (ref "C19") (pin "1") (pinfunction "+_1") (pintype "passive"))
      (node (ref "D5") (pin "2") (pinfunction "VLDOIN_2") (pintype "power_in"))
      (node (ref "R49") (pin "1") (pinfunction "+_1") (pintype "passive"))
      (node (ref "R58") (pin "1") (pinfunction "+_1") (pintype "passive"))
      (node (ref "U1") (pin "A1") (pinfunction "VDDQ_A1") (pintype "power_in"))
      (node (ref "U1") (pin "A8") (pinfunction "VDDQ_A8") (pintype "power_in"))
      (node (ref "U1") (pin "B2") (pinfunction "VDD_B2") (pintype "power_in"))
      (node (ref "U1") (pin "C1") (pinfunction "VDDQ_C1") (pintype "power_in"))
      (node (ref "U1") (pin "C9") (pinfunction "VDDQ_C9") (pintype "power_in"))
      (node (ref "U1") (pin "D2") (pinfunction "VDDQ_D2") (pintype "power_in"))
      (node (ref "U1") (pin "D9") (pinfunction "VDD_D9") (pintype "power_in"))
      (node (ref "U1") (pin "E9") (pinfunction "VDDQ_E9") (pintype "power_in"))
      (node (ref "U1") (pin "F1") (pinfunction "VDDQ_F1") (pintype "power_in"))
      (node (ref "U1") (pin "G7") (pinfunction "VDD_G7") (pintype "power_in"))
      (node (ref "U1") (pin "H2") (pinfunction "VDDQ_H2") (pintype "power_in"))
      (node (ref "U1") (pin "H9") (pinfunction "VDDQ_H9") (pintype "power_in"))
      (node (ref "U1") (pin "K2") (pinfunction "VDD_K2") (pintype "power_in"))
      (node (ref "U1") (pin "K8") (pinfunction "VDD_K8") (pintype "power_in"))
      (node (ref "U1") (pin "N1") (pinfunction "VDD_N1") (pintype "power_in"))
      (node (ref "U1") (pin "N9") (pinfunction "VDD_N9") (pintype "power_in"))
      (node (ref "U1") (pin "R1") (pinfunction "VDD_R1") (pintype "power_in"))
      (node (ref "U1") (pin "R9") (pinfunction "VDD_R9") (pintype "power_in"))
      (node (ref "U2") (pin "A1") (pinfunction "VDDQ_A1") (pintype "power_in"))
      (node (ref "U2") (pin "A8") (pinfunction "VDDQ_A8") (pintype "power_in"))
      (node (ref "U2") (pin "B2") (pinfunction "VDD_B2") (pintype "power_in"))
      (node (ref "U2") (pin "C1") (pinfunction "VDDQ_C1") (pintype "power_in"))
      (node (ref "U2") (pin "C9") (pinfunction "VDDQ_C9") (pintype "power_in"))
      (node (ref "U2") (pin "D2") (pinfunction "VDDQ_D2") (pintype "power_in"))
      (node (ref "U2") (pin "D9") (pinfunction "VDD_D9") (pintype "power_in"))
      (node (ref "U2") (pin "E9") (pinfunction "VDDQ_E9") (pintype "power_in"))
      (node (ref "U2") (pin "F1") (pinfunction "VDDQ_F1") (pintype "power_in"))
      (node (ref "U2") (pin "G7") (pinfunction "VDD_G7") (pintype "power_in"))
      (node (ref "U2") (pin "H2") (pinfunction "VDDQ_H2") (pintype "power_in"))
      (node (ref "U2") (pin "H9") (pinfunction "VDDQ_H9") (pintype "power_in"))
      (node (ref "U2") (pin "K2") (pinfunction "VDD_K2") (pintype "power_in"))
      (node (ref "U2") (pin "K8") (pinfunction "VDD_K8") (pintype "power_in"))
      (node (ref "U2") (pin "N1") (pinfunction "VDD_N1") (pintype "power_in"))
      (node (ref "U2") (pin "N9") (pinfunction "VDD_N9") (pintype "power_in"))
      (node (ref "U2") (pin "R1") (pinfunction "VDD_R1") (pintype "power_in"))
      (node (ref "U2") (pin "R9") (pinfunction "VDD_R9") (pintype "power_in"))
    )
    (net (code "97") (name "VCC3P3") (class "Default")
      (node (ref "C16") (pin "1") (pinfunction "+_1") (pintype "passive"))
      (node (ref "D5") (pin "10") (pinfunction "VIN_10") (pintype "power_in"))
      (node (ref "R55") (pin "1") (pinfunction "+_1") (pintype "passive"))
      (node (ref "R56") (pin "1") (pinfunction "+_1") (pintype "passive"))
    )
    (net (code "98") (name "unconnected-(D2B-CLK1n-PadY16)") (class "Default")
      (node (ref "D2") (pin "Y16") (pinfunction "CLK1n_Y16") (pintype "bidirectional"))
    )
    (net (code "99") (name "unconnected-(D2B-DIFFIO_RX_B18n-PadAG11)") (class "Default")
      (node (ref "D2") (pin "AG11") (pinfunction "DIFFIO_RX_B18n_AG11") (pintype "bidirectional"))
    )
    (net (code "100") (name "unconnected-(D2B-DIFFIO_TX_B17n-PadAH9)") (class "Default")
      (node (ref "D2") (pin "AH9") (pinfunction "DIFFIO_TX_B17n_AH9") (pintype "bidirectional+no_connect"))
    )
    (net (code "101") (name "unconnected-(D2B-DIFFIO_TX_B17p-PadAG10)") (class "Default")
      (node (ref "D2") (pin "AG10") (pinfunction "DIFFIO_TX_B17p_AG10") (pintype "bidirectional+no_connect"))
    )
    (net (code "102") (name "unconnected-(D2B-DIFFIO_TX_B20n-PadAK3)") (class "Default")
      (node (ref "D2") (pin "AK3") (pinfunction "DIFFIO_TX_B20n_AK3") (pintype "bidirectional+no_connect"))
    )
    (net (code "103") (name "unconnected-(D2B-DIFFIO_TX_B20p-PadAK2)") (class "Default")
      (node (ref "D2") (pin "AK2") (pinfunction "DIFFIO_TX_B20p_AK2") (pintype "bidirectional+no_connect"))
    )
    (net (code "104") (name "unconnected-(D2B-DIFFIO_TX_B21n-PadAK4)") (class "Default")
      (node (ref "D2") (pin "AK4") (pinfunction "DIFFIO_TX_B21n_AK4") (pintype "bidirectional+no_connect"))
    )
    (net (code "105") (name "unconnected-(D2B-DIFFIO_TX_B21p-PadAJ4)") (class "Default")
      (node (ref "D2") (pin "AJ4") (pinfunction "DIFFIO_TX_B21p_AJ4") (pintype "bidirectional+no_connect"))
    )
    (net (code "106") (name "unconnected-(D2B-DIFFIO_TX_B24n-PadAK6)") (class "Default")
      (node (ref "D2") (pin "AK6") (pinfunction "DIFFIO_TX_B24n_AK6") (pintype "bidirectional+no_connect"))
    )
    (net (code "107") (name "unconnected-(D2B-DIFFIO_TX_B24p-PadAJ5)") (class "Default")
      (node (ref "D2") (pin "AJ5") (pinfunction "DIFFIO_TX_B24p_AJ5") (pintype "bidirectional+no_connect"))
    )
    (net (code "108") (name "unconnected-(D2B-IO-PadAC14)") (class "Default")
      (node (ref "D2") (pin "AC14") (pinfunction "IO_AC14") (pintype "bidirectional+no_connect"))
    )
    (net (code "109") (name "unconnected-(D2B-IO-PadAG13)") (class "Default")
      (node (ref "D2") (pin "AG13") (pinfunction "IO_AG13") (pintype "bidirectional+no_connect"))
    )
    (net (code "110") (name "unconnected-(D2C-CLK2n-PadAB17)") (class "Default")
      (node (ref "D2") (pin "AB17") (pinfunction "CLK2n_AB17") (pintype "bidirectional"))
    )
    (net (code "111") (name "unconnected-(D2C-CLK3n-PadAD17)") (class "Default")
      (node (ref "D2") (pin "AD17") (pinfunction "CLK3n_AD17") (pintype "bidirectional"))
    )
    (net (code "112") (name "unconnected-(D2C-CLK3p-PadAC18)") (class "Default")
      (node (ref "D2") (pin "AC18") (pinfunction "CLK3p_AC18") (pintype "bidirectional"))
    )
    (net (code "113") (name "unconnected-(D2C-DIFFIO_RX_B74n-PadAD21)") (class "Default")
      (node (ref "D2") (pin "AD21") (pinfunction "DIFFIO_RX_B74n_AD21") (pintype "bidirectional+no_connect"))
    )
    (net (code "114") (name "unconnected-(D2C-DIFFIO_RX_B74p-PadAD20)") (class "Default")
      (node (ref "D2") (pin "AD20") (pinfunction "DIFFIO_RX_B74p_AD20") (pintype "bidirectional+no_connect"))
    )
    (net (code "115") (name "unconnected-(D2C-DIFFIO_RX_B75n-PadAA20)") (class "Default")
      (node (ref "D2") (pin "AA20") (pinfunction "DIFFIO_RX_B75n_AA20") (pintype "bidirectional+no_connect"))
    )
    (net (code "116") (name "unconnected-(D2C-DIFFIO_RX_B75p-PadY19)") (class "Default")
      (node (ref "D2") (pin "Y19") (pinfunction "DIFFIO_RX_B75p_Y19") (pintype "bidirectional+no_connect"))
    )
    (net (code "117") (name "unconnected-(D2C-DIFFIO_RX_B78n-PadAC23)") (class "Default")
      (node (ref "D2") (pin "AC23") (pinfunction "DIFFIO_RX_B78n_AC23") (pintype "bidirectional+no_connect"))
    )
    (net (code "118") (name "unconnected-(D2C-DIFFIO_RX_B78p-PadAC22)") (class "Default")
      (node (ref "D2") (pin "AC22") (pinfunction "DIFFIO_RX_B78p_AC22") (pintype "bidirectional+no_connect"))
    )
    (net (code "119") (name "unconnected-(D2C-DIFFIO_TX_B80n-PadAE24)") (class "Default")
      (node (ref "D2") (pin "AE24") (pinfunction "DIFFIO_TX_B80n_AE24") (pintype "bidirectional+no_connect"))
    )
    (net (code "120") (name "unconnected-(D2C-DIFFIO_TX_B80p-PadAD24)") (class "Default")
      (node (ref "D2") (pin "AD24") (pinfunction "DIFFIO_TX_B80p_AD24") (pintype "bidirectional+no_connect"))
    )
    (net (code "121") (name "unconnected-(D2C-GND-PadAA19)") (class "Default")
      (node (ref "D2") (pin "AA19") (pinfunction "GND_AA19") (pintype "bidirectional"))
    )
    (net (code "122") (name "unconnected-(D2C-GND-PadAA21)") (class "Default")
      (node (ref "D2") (pin "AA21") (pinfunction "GND_AA21") (pintype "bidirectional"))
    )
    (net (code "123") (name "unconnected-(D2C-GND-PadAB21)") (class "Default")
      (node (ref "D2") (pin "AB21") (pinfunction "GND_AB21") (pintype "bidirectional"))
    )
    (net (code "124") (name "unconnected-(D2C-GND-PadAF26)") (class "Default")
      (node (ref "D2") (pin "AF26") (pinfunction "GND_AF26") (pintype "bidirectional"))
    )
    (net (code "125") (name "unconnected-(D2C-GND-PadAG26)") (class "Default")
      (node (ref "D2") (pin "AG26") (pinfunction "GND_AG26") (pintype "bidirectional"))
    )
    (net (code "126") (name "unconnected-(D2C-GND-PadAH19)") (class "Default")
      (node (ref "D2") (pin "AH19") (pinfunction "GND_AH19") (pintype "bidirectional"))
    )
    (net (code "127") (name "unconnected-(D2C-GND-PadAH22)") (class "Default")
      (node (ref "D2") (pin "AH22") (pinfunction "GND_AH22") (pintype "bidirectional"))
    )
    (net (code "128") (name "unconnected-(D2C-GND-PadAH25)") (class "Default")
      (node (ref "D2") (pin "AH25") (pinfunction "GND_AH25") (pintype "bidirectional"))
    )
    (net (code "129") (name "unconnected-(D2C-GND-PadAJ25)") (class "Default")
      (node (ref "D2") (pin "AJ25") (pinfunction "GND_AJ25") (pintype "bidirectional"))
    )
    (net (code "130") (name "unconnected-(D2C-GND-PadAJ26)") (class "Default")
      (node (ref "D2") (pin "AJ26") (pinfunction "GND_AJ26") (pintype "bidirectional"))
    )
    (net (code "131") (name "unconnected-(D2C-GND-PadAK29)") (class "Default")
      (node (ref "D2") (pin "AK29") (pinfunction "GND_AK29") (pintype "bidirectional"))
    )
    (net (code "132") (name "unconnected-(D2C-GND-PadV18)") (class "Default")
      (node (ref "D2") (pin "V18") (pinfunction "GND_V18") (pintype "bidirectional"))
    )
    (net (code "133") (name "unconnected-(D2C-GND-PadW19)") (class "Default")
      (node (ref "D2") (pin "W19") (pinfunction "GND_W19") (pintype "bidirectional"))
    )
    (net (code "134") (name "unconnected-(D2C-GND-PadY18)") (class "Default")
      (node (ref "D2") (pin "Y18") (pinfunction "GND_Y18") (pintype "bidirectional"))
    )
    (net (code "135") (name "unconnected-(D2C-IO-PadAF25)") (class "Default")
      (node (ref "D2") (pin "AF25") (pinfunction "IO_AF25") (pintype "bidirectional+no_connect"))
    )
    (net (code "136") (name "unconnected-(D2C-IO-PadAH27)") (class "Default")
      (node (ref "D2") (pin "AH27") (pinfunction "IO_AH27") (pintype "bidirectional+no_connect"))
    )
    (net (code "137") (name "unconnected-(D2C-IO-PadAJ19)") (class "Default")
      (node (ref "D2") (pin "AJ19") (pinfunction "IO_AJ19") (pintype "bidirectional+no_connect"))
    )
    (net (code "138") (name "unconnected-(D2C-IO-PadAK16)") (class "Default")
      (node (ref "D2") (pin "AK16") (pinfunction "IO_AK16") (pintype "bidirectional+no_connect"))
    )
    (net (code "139") (name "unconnected-(D2C-IO-PadAK28)") (class "Default")
      (node (ref "D2") (pin "AK28") (pinfunction "IO_AK28") (pintype "bidirectional+no_connect"))
    )
    (net (code "140") (name "unconnected-(U1C-NC-PadJ1)") (class "Default")
      (node (ref "U1") (pin "J1") (pinfunction "NC_J1") (pintype "passive"))
    )
    (net (code "141") (name "unconnected-(U1C-NC-PadJ9)") (class "Default")
      (node (ref "U1") (pin "J9") (pinfunction "NC_J9") (pintype "passive"))
    )
    (net (code "142") (name "unconnected-(U1C-NC-PadL1)") (class "Default")
      (node (ref "U1") (pin "L1") (pinfunction "NC_L1") (pintype "passive"))
    )
    (net (code "143") (name "unconnected-(U1C-NC-PadL9)") (class "Default")
      (node (ref "U1") (pin "L9") (pinfunction "NC_L9") (pintype "passive"))
    )
    (net (code "144") (name "unconnected-(U1C-NC-PadM7)") (class "Default")
      (node (ref "U1") (pin "M7") (pinfunction "NC_M7") (pintype "passive"))
    )
    (net (code "145") (name "unconnected-(U2C-NC-PadJ1)") (class "Default")
      (node (ref "U2") (pin "J1") (pinfunction "NC_J1") (pintype "passive"))
    )
    (net (code "146") (name "unconnected-(U2C-NC-PadJ9)") (class "Default")
      (node (ref "U2") (pin "J9") (pinfunction "NC_J9") (pintype "passive"))
    )
    (net (code "147") (name "unconnected-(U2C-NC-PadL1)") (class "Default")
      (node (ref "U2") (pin "L1") (pinfunction "NC_L1") (pintype "passive"))
    )
    (net (code "148") (name "unconnected-(U2C-NC-PadL9)") (class "Default")
      (node (ref "U2") (pin "L9") (pinfunction "NC_L9") (pintype "passive"))
    )
    (net (code "149") (name "unconnected-(U2C-NC-PadM7)") (class "Default")
      (node (ref "U2") (pin "M7") (pinfunction "NC_M7") (pintype "passive"))
    )
  )
)
